# OpIoT_jetson_v_1_4.net
KiCad netlist of a schematic drawn in EAGLE
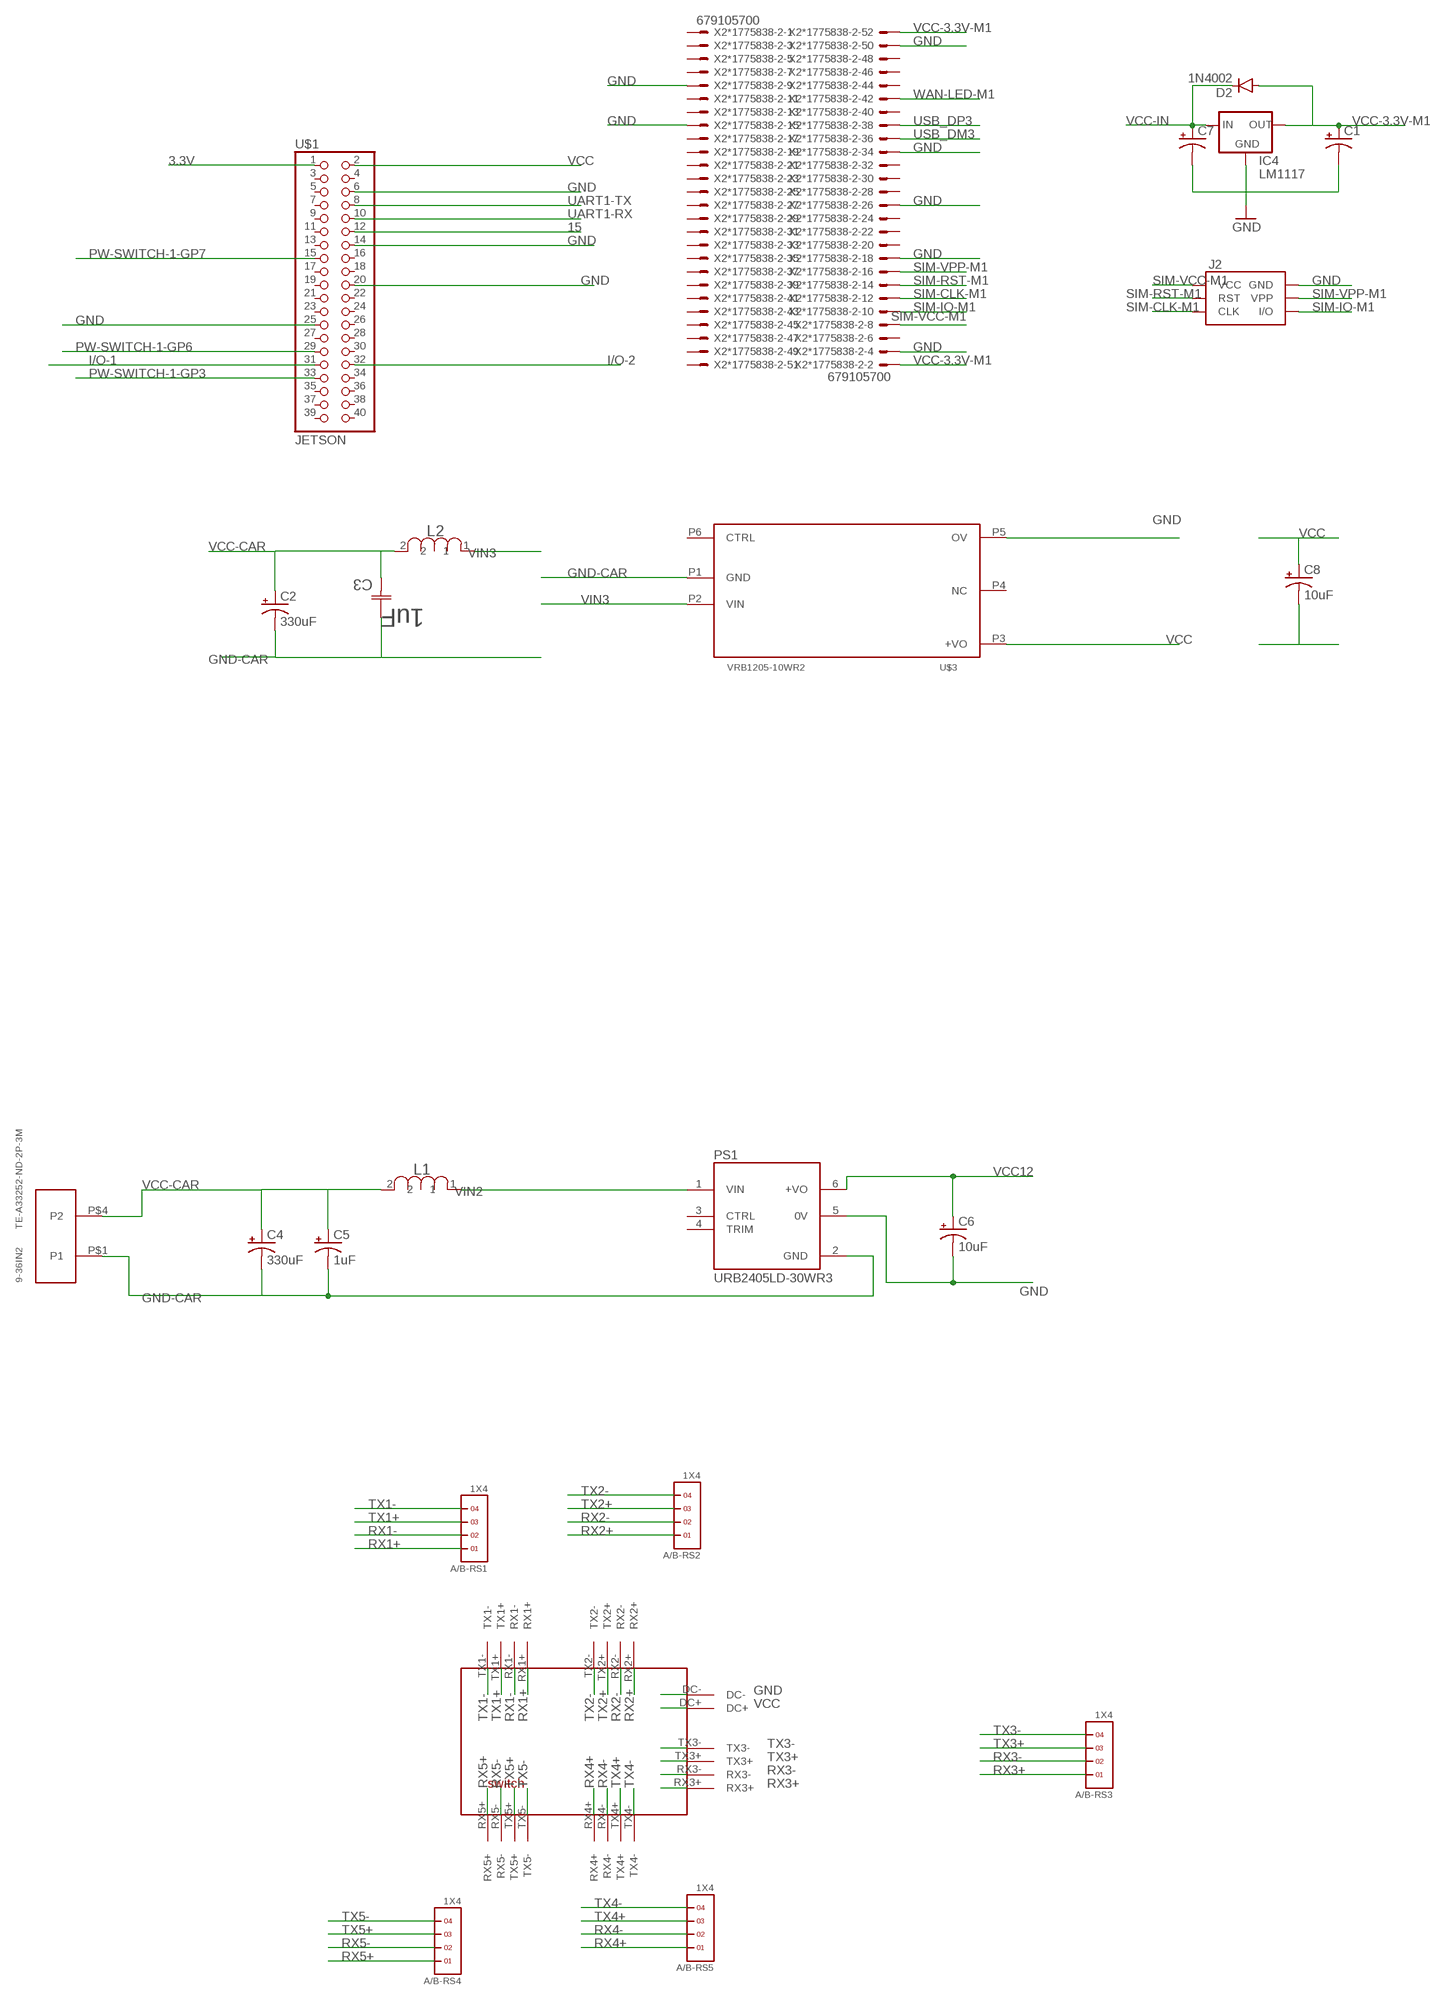
[diagram p0: schematic, sheet 1, part 1 of 2]
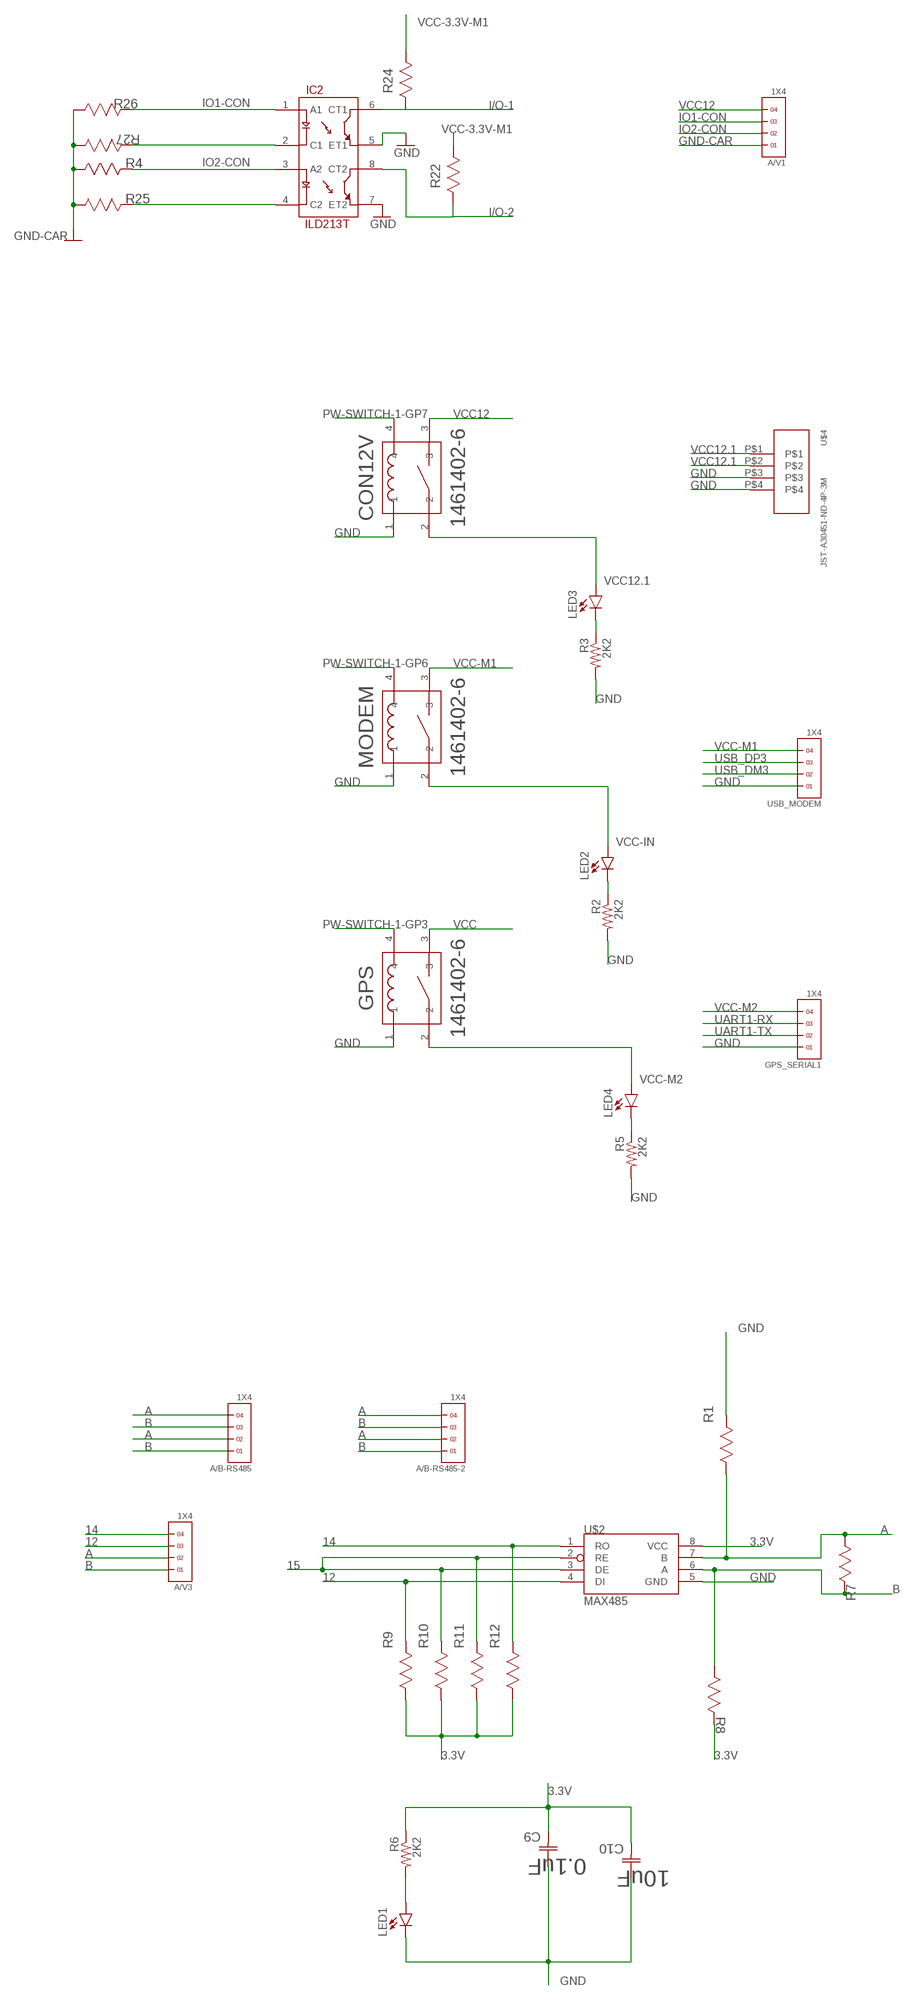
[diagram p1: schematic, sheet 1, part 2 of 2]

(export (version "E")
  (design (tool "Eeschema 10.0.6"))
  (components
    (comp (ref "9-36IN2")
      (value "TE-A33252-ND-2P-3M")
      (footprint "eagle-import:TE-A33252-ND-2P-3M")
      (libsource (lib "eagle-import") (part "TE-A33252-ND-2P-3M"))
    )
    (comp (ref "A/B-RS1")
      (value "1X4")
      (footprint "eagle-import:1X4")
      (libsource (lib "eagle-import") (part "1X4"))
    )
    (comp (ref "A/B-RS2")
      (value "1X4")
      (footprint "eagle-import:1X4")
      (libsource (lib "eagle-import") (part "1X4"))
    )
    (comp (ref "A/B-RS3")
      (value "1X4")
      (footprint "eagle-import:1X4")
      (libsource (lib "eagle-import") (part "1X4"))
    )
    (comp (ref "A/B-RS4")
      (value "1X4")
      (footprint "eagle-import:1X4")
      (libsource (lib "eagle-import") (part "1X4"))
    )
    (comp (ref "A/B-RS5")
      (value "1X4")
      (footprint "eagle-import:1X4")
      (libsource (lib "eagle-import") (part "1X4"))
    )
    (comp (ref "A/B-RS485")
      (value "1X4")
      (footprint "eagle-import:1X4")
      (libsource (lib "eagle-import") (part "1X4"))
    )
    (comp (ref "A/B-RS485-2")
      (value "1X4")
      (footprint "eagle-import:1X4")
      (libsource (lib "eagle-import") (part "1X4"))
    )
    (comp (ref "A/V1")
      (value "1X4")
      (footprint "eagle-import:1X4")
      (libsource (lib "eagle-import") (part "1X4"))
    )
    (comp (ref "A/V3")
      (value "1X4")
      (footprint "eagle-import:1X4")
      (libsource (lib "eagle-import") (part "1X4"))
    )
    (comp (ref "C1")
      (value "CAP_POL1206-KIT")
      (footprint "eagle-import:EIA3216-KIT")
      (libsource (lib "eagle-import") (part "CAP_POL1206-KIT"))
    )
    (comp (ref "C2")
      (value "330uF")
      (footprint "eagle-import:UD-10X10_NICHICON")
      (libsource (lib "eagle-import") (part "CPOL-USUD-10X10"))
    )
    (comp (ref "C3")
      (value "1uF")
      (footprint "eagle-import:CAPC3216X110N")
      (fields (field (name "MPN") "C1206C105K5RACTU") (field (name "TOLERANCE") "±10%"))
      (libsource (lib "eagle-import") (part "C1206C105K5RACTU"))
    )
    (comp (ref "C4")
      (value "330uF")
      (footprint "eagle-import:UD-10X10_NICHICON")
      (libsource (lib "eagle-import") (part "CPOL-USUD-10X10"))
    )
    (comp (ref "C5")
      (value "1uF")
      (footprint "eagle-import:EIA3216-KIT")
      (libsource (lib "eagle-import") (part "CAP_POL1206-KIT"))
    )
    (comp (ref "C6")
      (value "10uF")
      (footprint "eagle-import:EIA3216-KIT")
      (libsource (lib "eagle-import") (part "CAP_POL1206-KIT"))
    )
    (comp (ref "C7")
      (value "CAP_POL1206-KIT")
      (footprint "eagle-import:EIA3216-KIT")
      (libsource (lib "eagle-import") (part "CAP_POL1206-KIT"))
    )
    (comp (ref "C8")
      (value "10uF")
      (footprint "eagle-import:EIA3216-KIT")
      (libsource (lib "eagle-import") (part "CAP_POL1206-KIT"))
    )
    (comp (ref "C9")
      (value "0.1uF")
      (footprint "eagle-import:CAPC3216X110N")
      (fields (field (name "MPN") "C1206C105K5RACTU") (field (name "TOLERANCE") "±10%"))
      (libsource (lib "eagle-import") (part "C1206C105K5RACTU"))
    )
    (comp (ref "C10")
      (value "10uF")
      (footprint "eagle-import:CAPC3216X110N")
      (fields (field (name "MPN") "C1206C105K5RACTU") (field (name "TOLERANCE") "±10%"))
      (libsource (lib "eagle-import") (part "C1206C105K5RACTU"))
    )
    (comp (ref "CON12V")
      (value "1461402-6")
      (footprint "eagle-import:RELAY_1461402-6")
      (fields (field (name "MF") "TE Connectivity") (field (name "MP") "OJE-SH-112HM,000"))
      (libsource (lib "eagle-import") (part "1461402-6"))
    )
    (comp (ref "D2")
      (value "1N4002")
      (footprint "eagle-import:SMA-DIODE-KIT")
      (libsource (lib "eagle-import") (part "DIODESMA-KIT"))
    )
    (comp (ref "GPS")
      (value "1461402-6")
      (footprint "eagle-import:RELAY_1461402-6")
      (fields (field (name "MF") "TE Connectivity") (field (name "MP") "OJE-SH-112HM,000"))
      (libsource (lib "eagle-import") (part "1461402-6"))
    )
    (comp (ref "GPS_SERIAL1")
      (value "1X4")
      (footprint "eagle-import:1X4")
      (libsource (lib "eagle-import") (part "1X4"))
    )
    (comp (ref "IC2")
      (value "ILD213T")
      (footprint "eagle-import:SO08")
      (libsource (lib "eagle-import") (part "ILD213T"))
    )
    (comp (ref "IC4")
      (value "LM1117")
      (footprint "eagle-import:SOT223")
      (fields (field (name "MF") "Texas Instruments") (field (name "MP") "LM1117MP-3.3/NOPB"))
      (libsource (lib "eagle-import") (part "LM1117"))
    )
    (comp (ref "J2")
      (value "SIMHOLDERSIM")
      (footprint "eagle-import:SIMHOLDER")
      (libsource (lib "eagle-import") (part "SIMHOLDERSIM"))
    )
    (comp (ref "L1")
      (value "4.7uH")
      (footprint "eagle-import:INDC3225X22N")
      (fields (field (name "MPN") "PM1210-1R0J-RC") (field (name "TOLERANCE") "±5 %"))
      (libsource (lib "eagle-import") (part "PM1210-1R0J-RC"))
    )
    (comp (ref "L2")
      (value "4.7uH")
      (footprint "eagle-import:INDC3225X22N")
      (fields (field (name "MPN") "PM1210-1R0J-RC") (field (name "TOLERANCE") "±5 %"))
      (libsource (lib "eagle-import") (part "PM1210-1R0J-RC"))
    )
    (comp (ref "LED1")
      (value "LEDCHIPLED_1206")
      (footprint "eagle-import:CHIPLED_1206")
      (libsource (lib "eagle-import") (part "LEDCHIPLED_1206"))
    )
    (comp (ref "LED2")
      (value "LEDCHIPLED_1206")
      (footprint "eagle-import:CHIPLED_1206")
      (libsource (lib "eagle-import") (part "LEDCHIPLED_1206"))
    )
    (comp (ref "LED3")
      (value "LEDCHIPLED_1206")
      (footprint "eagle-import:CHIPLED_1206")
      (libsource (lib "eagle-import") (part "LEDCHIPLED_1206"))
    )
    (comp (ref "LED4")
      (value "LEDCHIPLED_1206")
      (footprint "eagle-import:CHIPLED_1206")
      (libsource (lib "eagle-import") (part "LEDCHIPLED_1206"))
    )
    (comp (ref "MODEM")
      (value "1461402-6")
      (footprint "eagle-import:RELAY_1461402-6")
      (fields (field (name "MF") "TE Connectivity") (field (name "MP") "OJE-SH-112HM,000"))
      (libsource (lib "eagle-import") (part "1461402-6"))
    )
    (comp (ref "PS1")
      (value "URB2405LD-30WR3")
      (footprint "eagle-import:CONV_URB2405LD-30WR3")
      (fields (field (name "MF") "MORNSUN"))
      (libsource (lib "eagle-import") (part "URB2405LD-30WR3"))
    )
    (comp (ref "R1")
      (value "20K")
      (footprint "eagle-import:RESC3216X71N")
      (fields (field (name "MPN") "ERJ-8ENF1501V") (field (name "TOLERANCE") "±1 %"))
      (libsource (lib "eagle-import") (part "ERJ-8ENF1501V"))
    )
    (comp (ref "R2")
      (value "2K2")
      (footprint "eagle-import:M1206")
      (libsource (lib "eagle-import") (part "R-US_M1206"))
    )
    (comp (ref "R3")
      (value "2K2")
      (footprint "eagle-import:M1206")
      (libsource (lib "eagle-import") (part "R-US_M1206"))
    )
    (comp (ref "R4")
      (value "4K7")
      (footprint "eagle-import:RESC3216X71N")
      (fields (field (name "MPN") "ERJ-8ENF1501V") (field (name "TOLERANCE") "±1 %"))
      (libsource (lib "eagle-import") (part "ERJ-8ENF1501V"))
    )
    (comp (ref "R5")
      (value "2K2")
      (footprint "eagle-import:M1206")
      (libsource (lib "eagle-import") (part "R-US_M1206"))
    )
    (comp (ref "R6")
      (value "2K2")
      (footprint "eagle-import:M1206")
      (libsource (lib "eagle-import") (part "R-US_M1206"))
    )
    (comp (ref "R7")
      (value "120")
      (footprint "eagle-import:RESC3216X71N")
      (fields (field (name "MPN") "ERJ-8ENF1501V") (field (name "TOLERANCE") "±1 %"))
      (libsource (lib "eagle-import") (part "ERJ-8ENF1501V"))
    )
    (comp (ref "R8")
      (value "20k")
      (footprint "eagle-import:RESC3216X71N")
      (fields (field (name "MPN") "ERJ-8ENF1501V") (field (name "TOLERANCE") "±1 %"))
      (libsource (lib "eagle-import") (part "ERJ-8ENF1501V"))
    )
    (comp (ref "R9")
      (value "10k")
      (footprint "eagle-import:RESC3216X71N")
      (fields (field (name "MPN") "ERJ-8ENF1501V") (field (name "TOLERANCE") "±1 %"))
      (libsource (lib "eagle-import") (part "ERJ-8ENF1501V"))
    )
    (comp (ref "R10")
      (value "10k")
      (footprint "eagle-import:RESC3216X71N")
      (fields (field (name "MPN") "ERJ-8ENF1501V") (field (name "TOLERANCE") "±1 %"))
      (libsource (lib "eagle-import") (part "ERJ-8ENF1501V"))
    )
    (comp (ref "R11")
      (value "10k")
      (footprint "eagle-import:RESC3216X71N")
      (fields (field (name "MPN") "ERJ-8ENF1501V") (field (name "TOLERANCE") "±1 %"))
      (libsource (lib "eagle-import") (part "ERJ-8ENF1501V"))
    )
    (comp (ref "R12")
      (value "10k")
      (footprint "eagle-import:RESC3216X71N")
      (fields (field (name "MPN") "ERJ-8ENF1501V") (field (name "TOLERANCE") "±1 %"))
      (libsource (lib "eagle-import") (part "ERJ-8ENF1501V"))
    )
    (comp (ref "R22")
      (value "300K")
      (footprint "eagle-import:RESC3216X71N")
      (fields (field (name "MPN") "ERJ-8ENF1501V") (field (name "TOLERANCE") "±1 %"))
      (libsource (lib "eagle-import") (part "ERJ-8ENF1501V"))
    )
    (comp (ref "R24")
      (value "300K")
      (footprint "eagle-import:RESC3216X71N")
      (fields (field (name "MPN") "ERJ-8ENF1501V") (field (name "TOLERANCE") "±1 %"))
      (libsource (lib "eagle-import") (part "ERJ-8ENF1501V"))
    )
    (comp (ref "R25")
      (value "2.2K")
      (footprint "eagle-import:RESC3216X71N")
      (fields (field (name "MPN") "ERJ-8ENF1501V") (field (name "TOLERANCE") "±1 %"))
      (libsource (lib "eagle-import") (part "ERJ-8ENF1501V"))
    )
    (comp (ref "R26")
      (value "4K7")
      (footprint "eagle-import:RESC3216X71N")
      (fields (field (name "MPN") "ERJ-8ENF1501V") (field (name "TOLERANCE") "±1 %"))
      (libsource (lib "eagle-import") (part "ERJ-8ENF1501V"))
    )
    (comp (ref "R27")
      (value "2.2K")
      (footprint "eagle-import:RESC3216X71N")
      (fields (field (name "MPN") "ERJ-8ENF1501V") (field (name "TOLERANCE") "±1 %"))
      (libsource (lib "eagle-import") (part "ERJ-8ENF1501V"))
    )
    (comp (ref "U$1")
      (value "JETSON")
      (footprint "eagle-import:2X20")
      (libsource (lib "eagle-import") (part "JETSON"))
    )
    (comp (ref "U$2")
      (value "MAX485")
      (footprint "eagle-import:SO08")
      (fields (field (name "MF") "Maxim Integrated"))
      (libsource (lib "eagle-import") (part "MAX485"))
    )
    (comp (ref "U$3")
      (value "VRB1205-10WR2")
      (footprint "eagle-import:MORNSUN-5V")
      (libsource (lib "eagle-import") (part "VRB1205-10WR2"))
    )
    (comp (ref "U$4")
      (value "JST-A30451-ND-4P-3M")
      (footprint "eagle-import:TE-A30451-4P-TH-3M")
      (libsource (lib "eagle-import") (part "JST-A30451-ND-4P-3M"))
    )
    (comp (ref "U$6")
      (value "SWITCH")
      (footprint "eagle-import:JP4")
      (libsource (lib "eagle-import") (part "SWITCH"))
    )
    (comp (ref "USB_MODEM")
      (value "1X4")
      (footprint "eagle-import:1X4")
      (libsource (lib "eagle-import") (part "1X4"))
    )
    (comp (ref "X2*1775838-2")
      (value "679105700")
      (footprint "eagle-import:679105700")
      (fields (field (name "MF") "MOLEX") (field (name "MPN") "67910-5700"))
      (libsource (lib "eagle-import") (part "679105700"))
    )
  )
  (nets
    (net (code "1") (name "/3.3V") (class "Default")
      (node (ref "C10") (pin "2") (pinfunction "C2_2") (pintype "passive"))
      (node (ref "C9") (pin "2") (pinfunction "C2_2") (pintype "passive"))
      (node (ref "R10") (pin "2") (pinfunction "R2_2") (pintype "passive"))
      (node (ref "R11") (pin "2") (pinfunction "R2_2") (pintype "passive"))
      (node (ref "R12") (pin "2") (pinfunction "R2_2") (pintype "passive"))
      (node (ref "R6") (pin "1") (pinfunction "1_1") (pintype "passive"))
      (node (ref "R8") (pin "1") (pinfunction "R1_1") (pintype "passive"))
      (node (ref "R9") (pin "2") (pinfunction "R2_2") (pintype "passive"))
      (node (ref "U$1") (pin "1") (pinfunction "1_1") (pintype "passive"))
      (node (ref "U$2") (pin "8") (pinfunction "VCC_8") (pintype "bidirectional"))
    )
    (net (code "2") (name "/12") (class "Default")
      (node (ref "A/V3") (pin "3") (pinfunction "3_3") (pintype "bidirectional"))
      (node (ref "R9") (pin "1") (pinfunction "R1_1") (pintype "passive"))
      (node (ref "U$2") (pin "4") (pinfunction "DI_4") (pintype "bidirectional"))
    )
    (net (code "3") (name "/14") (class "Default")
      (node (ref "A/V3") (pin "4") (pinfunction "4_4") (pintype "bidirectional"))
      (node (ref "R12") (pin "1") (pinfunction "R1_1") (pintype "passive"))
      (node (ref "U$2") (pin "1") (pinfunction "RO_1") (pintype "bidirectional"))
    )
    (net (code "4") (name "/15") (class "Default")
      (node (ref "R10") (pin "1") (pinfunction "R1_1") (pintype "passive"))
      (node (ref "R11") (pin "1") (pinfunction "R1_1") (pintype "passive"))
      (node (ref "U$1") (pin "12") (pinfunction "12_12") (pintype "passive"))
      (node (ref "U$2") (pin "2") (pinfunction "RE_2") (pintype "bidirectional"))
      (node (ref "U$2") (pin "3") (pinfunction "DE_3") (pintype "bidirectional"))
    )
    (net (code "5") (name "/A") (class "Default")
      (node (ref "A/B-RS485") (pin "2") (pinfunction "2_2") (pintype "bidirectional"))
      (node (ref "A/B-RS485") (pin "4") (pinfunction "4_4") (pintype "bidirectional"))
      (node (ref "A/B-RS485-2") (pin "2") (pinfunction "2_2") (pintype "bidirectional"))
      (node (ref "A/B-RS485-2") (pin "4") (pinfunction "4_4") (pintype "bidirectional"))
      (node (ref "A/V3") (pin "2") (pinfunction "2_2") (pintype "bidirectional"))
      (node (ref "R1") (pin "2") (pinfunction "R2_2") (pintype "passive"))
      (node (ref "R7") (pin "1") (pinfunction "R1_1") (pintype "passive"))
      (node (ref "U$2") (pin "7") (pinfunction "B_7") (pintype "bidirectional"))
    )
    (net (code "6") (name "/B") (class "Default")
      (node (ref "A/B-RS485") (pin "1") (pinfunction "1_1") (pintype "bidirectional"))
      (node (ref "A/B-RS485") (pin "3") (pinfunction "3_3") (pintype "bidirectional"))
      (node (ref "A/B-RS485-2") (pin "1") (pinfunction "1_1") (pintype "bidirectional"))
      (node (ref "A/B-RS485-2") (pin "3") (pinfunction "3_3") (pintype "bidirectional"))
      (node (ref "A/V3") (pin "1") (pinfunction "1_1") (pintype "bidirectional"))
      (node (ref "R7") (pin "2") (pinfunction "R2_2") (pintype "passive"))
      (node (ref "R8") (pin "2") (pinfunction "R2_2") (pintype "passive"))
      (node (ref "U$2") (pin "6") (pinfunction "A_6") (pintype "bidirectional"))
    )
    (net (code "7") (name "/IO1-CON") (class "Default")
      (node (ref "A/V1") (pin "3") (pinfunction "3_3") (pintype "bidirectional"))
      (node (ref "IC2") (pin "1") (pinfunction "A1_1") (pintype "bidirectional"))
      (node (ref "R26") (pin "1") (pinfunction "R1_1") (pintype "passive"))
    )
    (net (code "8") (name "/IO2-CON") (class "Default")
      (node (ref "A/V1") (pin "2") (pinfunction "2_2") (pintype "bidirectional"))
      (node (ref "IC2") (pin "3") (pinfunction "A2_3") (pintype "bidirectional"))
      (node (ref "R4") (pin "1") (pinfunction "R1_1") (pintype "passive"))
    )
    (net (code "9") (name "/I{slash}O-1") (class "Default")
      (node (ref "IC2") (pin "6") (pinfunction "CT1_6") (pintype "bidirectional"))
      (node (ref "R24") (pin "2") (pinfunction "R2_2") (pintype "passive"))
      (node (ref "U$1") (pin "31") (pinfunction "31_31") (pintype "passive"))
    )
    (net (code "10") (name "/I{slash}O-2") (class "Default")
      (node (ref "IC2") (pin "8") (pinfunction "CT2_8") (pintype "bidirectional"))
      (node (ref "R22") (pin "2") (pinfunction "R2_2") (pintype "passive"))
      (node (ref "U$1") (pin "32") (pinfunction "32_32") (pintype "passive"))
    )
    (net (code "11") (name "/PW-SWITCH-1-GP3") (class "Default")
      (node (ref "GPS") (pin "4") (pinfunction "4_4") (pintype "passive"))
      (node (ref "U$1") (pin "33") (pinfunction "33_33") (pintype "passive"))
    )
    (net (code "12") (name "/PW-SWITCH-1-GP6") (class "Default")
      (node (ref "MODEM") (pin "4") (pinfunction "4_4") (pintype "passive"))
      (node (ref "U$1") (pin "29") (pinfunction "29_29") (pintype "passive"))
    )
    (net (code "13") (name "/PW-SWITCH-1-GP7") (class "Default")
      (node (ref "CON12V") (pin "4") (pinfunction "4_4") (pintype "passive"))
      (node (ref "U$1") (pin "15") (pinfunction "15_15") (pintype "passive"))
    )
    (net (code "14") (name "/RX1+") (class "Default")
      (node (ref "A/B-RS1") (pin "1") (pinfunction "1_1") (pintype "bidirectional"))
      (node (ref "U$6") (pin "RX1+") (pinfunction "RX1+_RX1+") (pintype "bidirectional"))
    )
    (net (code "15") (name "/RX1-") (class "Default")
      (node (ref "A/B-RS1") (pin "2") (pinfunction "2_2") (pintype "bidirectional"))
      (node (ref "U$6") (pin "RX1-") (pinfunction "RX1-_RX1-") (pintype "bidirectional"))
    )
    (net (code "16") (name "/RX2+") (class "Default")
      (node (ref "A/B-RS2") (pin "1") (pinfunction "1_1") (pintype "bidirectional"))
      (node (ref "U$6") (pin "RX2+") (pinfunction "RX2+_RX2+") (pintype "bidirectional"))
    )
    (net (code "17") (name "/RX2-") (class "Default")
      (node (ref "A/B-RS2") (pin "2") (pinfunction "2_2") (pintype "bidirectional"))
      (node (ref "U$6") (pin "RX2-") (pinfunction "RX2-_RX2-") (pintype "bidirectional"))
    )
    (net (code "18") (name "/RX3+") (class "Default")
      (node (ref "A/B-RS3") (pin "1") (pinfunction "1_1") (pintype "bidirectional"))
      (node (ref "U$6") (pin "RX3+") (pinfunction "RX3+_RX3+") (pintype "bidirectional"))
    )
    (net (code "19") (name "/RX3-") (class "Default")
      (node (ref "A/B-RS3") (pin "2") (pinfunction "2_2") (pintype "bidirectional"))
      (node (ref "U$6") (pin "RX3-") (pinfunction "RX3-_RX3-") (pintype "bidirectional"))
    )
    (net (code "20") (name "/RX4+") (class "Default")
      (node (ref "A/B-RS5") (pin "1") (pinfunction "1_1") (pintype "bidirectional"))
      (node (ref "U$6") (pin "RX4+") (pinfunction "RX4+_RX4+") (pintype "bidirectional"))
    )
    (net (code "21") (name "/RX4-") (class "Default")
      (node (ref "A/B-RS5") (pin "2") (pinfunction "2_2") (pintype "bidirectional"))
      (node (ref "U$6") (pin "RX4-") (pinfunction "RX4-_RX4-") (pintype "bidirectional"))
    )
    (net (code "22") (name "/RX5+") (class "Default")
      (node (ref "A/B-RS4") (pin "1") (pinfunction "1_1") (pintype "bidirectional"))
      (node (ref "U$6") (pin "RX5+") (pinfunction "RX5+_RX5+") (pintype "bidirectional"))
    )
    (net (code "23") (name "/RX5-") (class "Default")
      (node (ref "A/B-RS4") (pin "2") (pinfunction "2_2") (pintype "bidirectional"))
      (node (ref "U$6") (pin "RX5-") (pinfunction "RX5-_RX5-") (pintype "bidirectional"))
    )
    (net (code "24") (name "/SIM-CLK-M1") (class "Default")
      (node (ref "J2") (pin "C3") (pinfunction "CLK_C3") (pintype "input"))
      (node (ref "X2*1775838-2") (pin "12") (pinfunction "S_12") (pintype "passive"))
    )
    (net (code "25") (name "/SIM-IO-M1") (class "Default")
      (node (ref "J2") (pin "C7") (pinfunction "I/O_C7") (pintype "bidirectional"))
      (node (ref "X2*1775838-2") (pin "10") (pinfunction "S_10") (pintype "passive"))
    )
    (net (code "26") (name "/SIM-RST-M1") (class "Default")
      (node (ref "J2") (pin "C2") (pinfunction "RST_C2") (pintype "input"))
      (node (ref "X2*1775838-2") (pin "14") (pinfunction "S_14") (pintype "passive"))
    )
    (net (code "27") (name "/SIM-VCC-M1") (class "Default")
      (node (ref "J2") (pin "C1") (pinfunction "VCC_C1") (pintype "power_in"))
      (node (ref "X2*1775838-2") (pin "8") (pinfunction "S_8") (pintype "passive"))
    )
    (net (code "28") (name "/SIM-VPP-M1") (class "Default")
      (node (ref "J2") (pin "C6") (pinfunction "VPP_C6") (pintype "input"))
      (node (ref "X2*1775838-2") (pin "16") (pinfunction "S_16") (pintype "passive"))
    )
    (net (code "29") (name "/TX1+") (class "Default")
      (node (ref "A/B-RS1") (pin "3") (pinfunction "3_3") (pintype "bidirectional"))
      (node (ref "U$6") (pin "TX1+") (pinfunction "TX1+_TX1+") (pintype "bidirectional"))
    )
    (net (code "30") (name "/TX1-") (class "Default")
      (node (ref "A/B-RS1") (pin "4") (pinfunction "4_4") (pintype "bidirectional"))
      (node (ref "U$6") (pin "TX1-") (pinfunction "TX1-_TX1-") (pintype "bidirectional"))
    )
    (net (code "31") (name "/TX2+") (class "Default")
      (node (ref "A/B-RS2") (pin "3") (pinfunction "3_3") (pintype "bidirectional"))
      (node (ref "U$6") (pin "TX2+") (pinfunction "TX2+_TX2+") (pintype "bidirectional"))
    )
    (net (code "32") (name "/TX2-") (class "Default")
      (node (ref "A/B-RS2") (pin "4") (pinfunction "4_4") (pintype "bidirectional"))
      (node (ref "U$6") (pin "TX2-") (pinfunction "TX2-_TX2-") (pintype "bidirectional"))
    )
    (net (code "33") (name "/TX3+") (class "Default")
      (node (ref "A/B-RS3") (pin "3") (pinfunction "3_3") (pintype "bidirectional"))
      (node (ref "U$6") (pin "TX3+") (pinfunction "TX3+_TX3+") (pintype "bidirectional"))
    )
    (net (code "34") (name "/TX3-") (class "Default")
      (node (ref "A/B-RS3") (pin "4") (pinfunction "4_4") (pintype "bidirectional"))
      (node (ref "U$6") (pin "TX3-") (pinfunction "TX3-_TX3-") (pintype "bidirectional"))
    )
    (net (code "35") (name "/TX4+") (class "Default")
      (node (ref "A/B-RS5") (pin "3") (pinfunction "3_3") (pintype "bidirectional"))
      (node (ref "U$6") (pin "TX4+") (pinfunction "TX4+_TX4+") (pintype "bidirectional"))
    )
    (net (code "36") (name "/TX4-") (class "Default")
      (node (ref "A/B-RS5") (pin "4") (pinfunction "4_4") (pintype "bidirectional"))
      (node (ref "U$6") (pin "TX4-") (pinfunction "TX4-_TX4-") (pintype "bidirectional"))
    )
    (net (code "37") (name "/TX5+") (class "Default")
      (node (ref "A/B-RS4") (pin "3") (pinfunction "3_3") (pintype "bidirectional"))
      (node (ref "U$6") (pin "TX5+") (pinfunction "TX5+_TX5+") (pintype "bidirectional"))
    )
    (net (code "38") (name "/TX5-") (class "Default")
      (node (ref "A/B-RS4") (pin "4") (pinfunction "4_4") (pintype "bidirectional"))
      (node (ref "U$6") (pin "TX5-") (pinfunction "TX5-_TX5-") (pintype "bidirectional"))
    )
    (net (code "39") (name "/UART1-RX") (class "Default")
      (node (ref "GPS_SERIAL1") (pin "3") (pinfunction "3_3") (pintype "bidirectional"))
      (node (ref "U$1") (pin "10") (pinfunction "10_10") (pintype "passive"))
    )
    (net (code "40") (name "/UART1-TX") (class "Default")
      (node (ref "GPS_SERIAL1") (pin "2") (pinfunction "2_2") (pintype "bidirectional"))
      (node (ref "U$1") (pin "8") (pinfunction "8_8") (pintype "passive"))
    )
    (net (code "41") (name "/USB_DM3") (class "Default")
      (node (ref "USB_MODEM") (pin "2") (pinfunction "2_2") (pintype "bidirectional"))
      (node (ref "X2*1775838-2") (pin "36") (pinfunction "S_36") (pintype "passive"))
    )
    (net (code "42") (name "/USB_DP3") (class "Default")
      (node (ref "USB_MODEM") (pin "3") (pinfunction "3_3") (pintype "bidirectional"))
      (node (ref "X2*1775838-2") (pin "38") (pinfunction "S_38") (pintype "passive"))
    )
    (net (code "43") (name "/VCC") (class "Default")
      (node (ref "C8") (pin "A") (pinfunction "+_A") (pintype "passive"))
      (node (ref "GPS") (pin "3") (pinfunction "3_3") (pintype "passive"))
      (node (ref "U$1") (pin "2") (pinfunction "2_2") (pintype "passive"))
      (node (ref "U$3") (pin "P3") (pinfunction "+VO_P3") (pintype "output"))
      (node (ref "U$6") (pin "DC+") (pinfunction "DC+_DC+") (pintype "bidirectional"))
    )
    (net (code "44") (name "/VCC-3.3V-M1") (class "Default")
      (node (ref "C1") (pin "A") (pinfunction "+_A") (pintype "passive"))
      (node (ref "D2") (pin "A") (pinfunction "A_A") (pintype "passive"))
      (node (ref "IC4") (pin "2") (pinfunction "OUT_2") (pintype "passive"))
      (node (ref "R22") (pin "1") (pinfunction "R1_1") (pintype "passive"))
      (node (ref "R24") (pin "1") (pinfunction "R1_1") (pintype "passive"))
      (node (ref "X2*1775838-2") (pin "2") (pinfunction "S_2") (pintype "passive"))
      (node (ref "X2*1775838-2") (pin "52") (pinfunction "S_52") (pintype "passive"))
    )
    (net (code "45") (name "/VCC-CAR") (class "Default")
      (node (ref "9-36IN2") (pin "P$4") (pinfunction "P2_P$4") (pintype "bidirectional"))
      (node (ref "C2") (pin "+") (pinfunction "+_+") (pintype "passive"))
      (node (ref "C3") (pin "2") (pinfunction "C2_2") (pintype "passive"))
      (node (ref "C4") (pin "+") (pinfunction "+_+") (pintype "passive"))
      (node (ref "C5") (pin "A") (pinfunction "+_A") (pintype "passive"))
      (node (ref "L1") (pin "2") (pinfunction "2_2") (pintype "passive"))
      (node (ref "L2") (pin "2") (pinfunction "2_2") (pintype "passive"))
    )
    (net (code "46") (name "/VCC-IN") (class "Default")
      (node (ref "C7") (pin "A") (pinfunction "+_A") (pintype "passive"))
      (node (ref "D2") (pin "C") (pinfunction "C_C") (pintype "passive"))
      (node (ref "IC4") (pin "3") (pinfunction "IN_3") (pintype "input"))
      (node (ref "LED2") (pin "A") (pinfunction "A_A") (pintype "passive"))
      (node (ref "MODEM") (pin "2") (pinfunction "2_2") (pintype "passive"))
    )
    (net (code "47") (name "/VCC-M1") (class "Default")
      (node (ref "MODEM") (pin "3") (pinfunction "3_3") (pintype "passive"))
      (node (ref "USB_MODEM") (pin "4") (pinfunction "4_4") (pintype "bidirectional"))
    )
    (net (code "48") (name "/VCC-M2") (class "Default")
      (node (ref "GPS") (pin "2") (pinfunction "2_2") (pintype "passive"))
      (node (ref "GPS_SERIAL1") (pin "4") (pinfunction "4_4") (pintype "bidirectional"))
      (node (ref "LED4") (pin "A") (pinfunction "A_A") (pintype "passive"))
    )
    (net (code "49") (name "/VCC12") (class "Default")
      (node (ref "A/V1") (pin "4") (pinfunction "4_4") (pintype "bidirectional"))
      (node (ref "C6") (pin "A") (pinfunction "+_A") (pintype "passive"))
      (node (ref "CON12V") (pin "3") (pinfunction "3_3") (pintype "passive"))
      (node (ref "PS1") (pin "6") (pinfunction "+VO_6") (pintype "output"))
    )
    (net (code "50") (name "/VCC12.1") (class "Default")
      (node (ref "CON12V") (pin "2") (pinfunction "2_2") (pintype "passive"))
      (node (ref "LED3") (pin "A") (pinfunction "A_A") (pintype "passive"))
      (node (ref "U$4") (pin "P$1") (pinfunction "P$1_P$1") (pintype "bidirectional"))
      (node (ref "U$4") (pin "P$2") (pinfunction "P$2_P$2") (pintype "bidirectional"))
    )
    (net (code "51") (name "/VIN2") (class "Default")
      (node (ref "L1") (pin "1") (pinfunction "1_1") (pintype "passive"))
      (node (ref "PS1") (pin "1") (pinfunction "VIN_1") (pintype "input"))
    )
    (net (code "52") (name "/VIN3") (class "Default")
      (node (ref "L2") (pin "1") (pinfunction "1_1") (pintype "passive"))
      (node (ref "U$3") (pin "P2") (pinfunction "VIN_P2") (pintype "bidirectional"))
    )
    (net (code "53") (name "/WAN-LED-M1") (class "Default")
      (node (ref "X2*1775838-2") (pin "42") (pinfunction "S_42") (pintype "passive"))
    )
    (net (code "54") (name "GND") (class "Default")
      (node (ref "C1") (pin "C") (pinfunction "-_C") (pintype "passive"))
      (node (ref "C10") (pin "1") (pinfunction "C1_1") (pintype "passive"))
      (node (ref "C6") (pin "C") (pinfunction "-_C") (pintype "passive"))
      (node (ref "C7") (pin "C") (pinfunction "-_C") (pintype "passive"))
      (node (ref "C8") (pin "C") (pinfunction "-_C") (pintype "passive"))
      (node (ref "C9") (pin "1") (pinfunction "C1_1") (pintype "passive"))
      (node (ref "CON12V") (pin "1") (pinfunction "1_1") (pintype "passive"))
      (node (ref "GPS") (pin "1") (pinfunction "1_1") (pintype "passive"))
      (node (ref "GPS_SERIAL1") (pin "1") (pinfunction "1_1") (pintype "bidirectional"))
      (node (ref "IC2") (pin "5") (pinfunction "ET1_5") (pintype "bidirectional"))
      (node (ref "IC2") (pin "7") (pinfunction "ET2_7") (pintype "bidirectional"))
      (node (ref "IC4") (pin "1") (pinfunction "GND_1") (pintype "input"))
      (node (ref "J2") (pin "C5") (pinfunction "GND_C5") (pintype "power_in"))
      (node (ref "LED1") (pin "C") (pinfunction "C_C") (pintype "passive"))
      (node (ref "MODEM") (pin "1") (pinfunction "1_1") (pintype "passive"))
      (node (ref "PS1") (pin "5") (pinfunction "0V_5") (pintype "output"))
      (node (ref "R1") (pin "1") (pinfunction "R1_1") (pintype "passive"))
      (node (ref "R2") (pin "2") (pinfunction "2_2") (pintype "passive"))
      (node (ref "R3") (pin "2") (pinfunction "2_2") (pintype "passive"))
      (node (ref "R5") (pin "2") (pinfunction "2_2") (pintype "passive"))
      (node (ref "U$1") (pin "14") (pinfunction "14_14") (pintype "passive"))
      (node (ref "U$1") (pin "20") (pinfunction "20_20") (pintype "passive"))
      (node (ref "U$1") (pin "25") (pinfunction "25_25") (pintype "passive"))
      (node (ref "U$1") (pin "6") (pinfunction "6_6") (pintype "passive"))
      (node (ref "U$2") (pin "5") (pinfunction "GND_5") (pintype "bidirectional"))
      (node (ref "U$3") (pin "P5") (pinfunction "OV_P5") (pintype "output"))
      (node (ref "U$4") (pin "P$3") (pinfunction "P$3_P$3") (pintype "bidirectional"))
      (node (ref "U$4") (pin "P$4") (pinfunction "P$4_P$4") (pintype "bidirectional"))
      (node (ref "U$6") (pin "DC-") (pinfunction "DC-_DC-") (pintype "bidirectional"))
      (node (ref "USB_MODEM") (pin "1") (pinfunction "1_1") (pintype "bidirectional"))
      (node (ref "X2*1775838-2") (pin "15") (pinfunction "S_15") (pintype "passive"))
      (node (ref "X2*1775838-2") (pin "18") (pinfunction "S_18") (pintype "passive"))
      (node (ref "X2*1775838-2") (pin "26") (pinfunction "S_26") (pintype "passive"))
      (node (ref "X2*1775838-2") (pin "34") (pinfunction "S_34") (pintype "passive"))
      (node (ref "X2*1775838-2") (pin "4") (pinfunction "S_4") (pintype "passive"))
      (node (ref "X2*1775838-2") (pin "50") (pinfunction "S_50") (pintype "passive"))
      (node (ref "X2*1775838-2") (pin "9") (pinfunction "S_9") (pintype "passive"))
    )
    (net (code "55") (name "GND-CAR") (class "Default")
      (node (ref "9-36IN2") (pin "P$1") (pinfunction "P1_P$1") (pintype "bidirectional"))
      (node (ref "A/V1") (pin "1") (pinfunction "1_1") (pintype "bidirectional"))
      (node (ref "C2") (pin "-") (pinfunction "-_-") (pintype "passive"))
      (node (ref "C3") (pin "1") (pinfunction "C1_1") (pintype "passive"))
      (node (ref "C4") (pin "-") (pinfunction "-_-") (pintype "passive"))
      (node (ref "C5") (pin "C") (pinfunction "-_C") (pintype "passive"))
      (node (ref "PS1") (pin "2") (pinfunction "GND_2") (pintype "power_in"))
      (node (ref "R25") (pin "1") (pinfunction "R1_1") (pintype "passive"))
      (node (ref "R26") (pin "2") (pinfunction "R2_2") (pintype "passive"))
      (node (ref "R27") (pin "1") (pinfunction "R1_1") (pintype "passive"))
      (node (ref "R4") (pin "2") (pinfunction "R2_2") (pintype "passive"))
      (node (ref "U$3") (pin "P1") (pinfunction "GND_P1") (pintype "bidirectional"))
    )
    (net (code "56") (name "Net-(IC2-C1)") (class "Default")
      (node (ref "IC2") (pin "2") (pinfunction "C1_2") (pintype "bidirectional"))
      (node (ref "R27") (pin "2") (pinfunction "R2_2") (pintype "passive"))
    )
    (net (code "57") (name "Net-(IC2-C2)") (class "Default")
      (node (ref "IC2") (pin "4") (pinfunction "C2_4") (pintype "bidirectional"))
      (node (ref "R25") (pin "2") (pinfunction "R2_2") (pintype "passive"))
    )
    (net (code "58") (name "Net-(LED1-PadA)") (class "Default")
      (node (ref "LED1") (pin "A") (pinfunction "A_A") (pintype "passive"))
      (node (ref "R6") (pin "2") (pinfunction "2_2") (pintype "passive"))
    )
    (net (code "59") (name "Net-(LED2-PadC)") (class "Default")
      (node (ref "LED2") (pin "C") (pinfunction "C_C") (pintype "passive"))
      (node (ref "R2") (pin "1") (pinfunction "1_1") (pintype "passive"))
    )
    (net (code "60") (name "Net-(LED3-PadC)") (class "Default")
      (node (ref "LED3") (pin "C") (pinfunction "C_C") (pintype "passive"))
      (node (ref "R3") (pin "1") (pinfunction "1_1") (pintype "passive"))
    )
    (net (code "61") (name "Net-(LED4-PadC)") (class "Default")
      (node (ref "LED4") (pin "C") (pinfunction "C_C") (pintype "passive"))
      (node (ref "R5") (pin "1") (pinfunction "1_1") (pintype "passive"))
    )
    (net (code "62") (name "unconnected-(PS1-CTRL-Pad3)") (class "Default")
      (node (ref "PS1") (pin "3") (pinfunction "CTRL_3") (pintype "input"))
    )
    (net (code "63") (name "unconnected-(PS1-TRIM-Pad4)") (class "Default")
      (node (ref "PS1") (pin "4") (pinfunction "TRIM_4") (pintype "input"))
    )
    (net (code "64") (name "unconnected-(U$1-Pad3)") (class "Default")
      (node (ref "U$1") (pin "3") (pinfunction "3_3") (pintype "passive"))
    )
    (net (code "65") (name "unconnected-(U$1-Pad4)") (class "Default")
      (node (ref "U$1") (pin "4") (pinfunction "4_4") (pintype "passive"))
    )
    (net (code "66") (name "unconnected-(U$1-Pad5)") (class "Default")
      (node (ref "U$1") (pin "5") (pinfunction "5_5") (pintype "passive"))
    )
    (net (code "67") (name "unconnected-(U$1-Pad7)") (class "Default")
      (node (ref "U$1") (pin "7") (pinfunction "7_7") (pintype "passive"))
    )
    (net (code "68") (name "unconnected-(U$1-Pad9)") (class "Default")
      (node (ref "U$1") (pin "9") (pinfunction "9_9") (pintype "passive"))
    )
    (net (code "69") (name "unconnected-(U$1-Pad11)") (class "Default")
      (node (ref "U$1") (pin "11") (pinfunction "11_11") (pintype "passive"))
    )
    (net (code "70") (name "unconnected-(U$1-Pad13)") (class "Default")
      (node (ref "U$1") (pin "13") (pinfunction "13_13") (pintype "passive"))
    )
    (net (code "71") (name "unconnected-(U$1-Pad16)") (class "Default")
      (node (ref "U$1") (pin "16") (pinfunction "16_16") (pintype "passive"))
    )
    (net (code "72") (name "unconnected-(U$1-Pad17)") (class "Default")
      (node (ref "U$1") (pin "17") (pinfunction "17_17") (pintype "passive"))
    )
    (net (code "73") (name "unconnected-(U$1-Pad18)") (class "Default")
      (node (ref "U$1") (pin "18") (pinfunction "18_18") (pintype "passive"))
    )
    (net (code "74") (name "unconnected-(U$1-Pad19)") (class "Default")
      (node (ref "U$1") (pin "19") (pinfunction "19_19") (pintype "passive"))
    )
    (net (code "75") (name "unconnected-(U$1-Pad21)") (class "Default")
      (node (ref "U$1") (pin "21") (pinfunction "21_21") (pintype "passive"))
    )
    (net (code "76") (name "unconnected-(U$1-Pad22)") (class "Default")
      (node (ref "U$1") (pin "22") (pinfunction "22_22") (pintype "passive"))
    )
    (net (code "77") (name "unconnected-(U$1-Pad23)") (class "Default")
      (node (ref "U$1") (pin "23") (pinfunction "23_23") (pintype "passive"))
    )
    (net (code "78") (name "unconnected-(U$1-Pad24)") (class "Default")
      (node (ref "U$1") (pin "24") (pinfunction "24_24") (pintype "passive"))
    )
    (net (code "79") (name "unconnected-(U$1-Pad26)") (class "Default")
      (node (ref "U$1") (pin "26") (pinfunction "26_26") (pintype "passive"))
    )
    (net (code "80") (name "unconnected-(U$1-Pad27)") (class "Default")
      (node (ref "U$1") (pin "27") (pinfunction "27_27") (pintype "passive"))
    )
    (net (code "81") (name "unconnected-(U$1-Pad28)") (class "Default")
      (node (ref "U$1") (pin "28") (pinfunction "28_28") (pintype "passive"))
    )
    (net (code "82") (name "unconnected-(U$1-Pad30)") (class "Default")
      (node (ref "U$1") (pin "30") (pinfunction "30_30") (pintype "passive"))
    )
    (net (code "83") (name "unconnected-(U$1-Pad34)") (class "Default")
      (node (ref "U$1") (pin "34") (pinfunction "34_34") (pintype "passive"))
    )
    (net (code "84") (name "unconnected-(U$1-Pad35)") (class "Default")
      (node (ref "U$1") (pin "35") (pinfunction "35_35") (pintype "passive"))
    )
    (net (code "85") (name "unconnected-(U$1-Pad36)") (class "Default")
      (node (ref "U$1") (pin "36") (pinfunction "36_36") (pintype "passive"))
    )
    (net (code "86") (name "unconnected-(U$1-Pad37)") (class "Default")
      (node (ref "U$1") (pin "37") (pinfunction "37_37") (pintype "passive"))
    )
    (net (code "87") (name "unconnected-(U$1-Pad38)") (class "Default")
      (node (ref "U$1") (pin "38") (pinfunction "38_38") (pintype "passive"))
    )
    (net (code "88") (name "unconnected-(U$1-Pad39)") (class "Default")
      (node (ref "U$1") (pin "39") (pinfunction "39_39") (pintype "passive"))
    )
    (net (code "89") (name "unconnected-(U$1-Pad40)") (class "Default")
      (node (ref "U$1") (pin "40") (pinfunction "40_40") (pintype "passive"))
    )
    (net (code "90") (name "unconnected-(U$3-CTRL-PadP6)") (class "Default")
      (node (ref "U$3") (pin "P6") (pinfunction "CTRL_P6") (pintype "bidirectional"))
    )
    (net (code "91") (name "unconnected-(U$3-NC-PadP4)") (class "Default")
      (node (ref "U$3") (pin "P4") (pinfunction "NC_P4") (pintype "output"))
    )
    (net (code "92") (name "unconnected-(X2*1775838-2A-S-Pad1)") (class "Default")
      (node (ref "X2*1775838-2") (pin "1") (pinfunction "S_1") (pintype "passive"))
    )
    (net (code "93") (name "unconnected-(X2*1775838-2AA-S-Pad33)") (class "Default")
      (node (ref "X2*1775838-2") (pin "33") (pinfunction "S_33") (pintype "passive"))
    )
    (net (code "94") (name "unconnected-(X2*1775838-2AC-S-Pad35)") (class "Default")
      (node (ref "X2*1775838-2") (pin "35") (pinfunction "S_35") (pintype "passive"))
    )
    (net (code "95") (name "unconnected-(X2*1775838-2AE-S-Pad37)") (class "Default")
      (node (ref "X2*1775838-2") (pin "37") (pinfunction "S_37") (pintype "passive"))
    )
    (net (code "96") (name "unconnected-(X2*1775838-2AG-S-Pad39)") (class "Default")
      (node (ref "X2*1775838-2") (pin "39") (pinfunction "S_39") (pintype "passive"))
    )
    (net (code "97") (name "unconnected-(X2*1775838-2AI-S-Pad40)") (class "Default")
      (node (ref "X2*1775838-2") (pin "40") (pinfunction "S_40") (pintype "passive"))
    )
    (net (code "98") (name "unconnected-(X2*1775838-2AJ-S-Pad41)") (class "Default")
      (node (ref "X2*1775838-2") (pin "41") (pinfunction "S_41") (pintype "passive"))
    )
    (net (code "99") (name "unconnected-(X2*1775838-2AL-S-Pad43)") (class "Default")
      (node (ref "X2*1775838-2") (pin "43") (pinfunction "S_43") (pintype "passive"))
    )
    (net (code "100") (name "unconnected-(X2*1775838-2AM-S-Pad44)") (class "Default")
      (node (ref "X2*1775838-2") (pin "44") (pinfunction "S_44") (pintype "passive"))
    )
    (net (code "101") (name "unconnected-(X2*1775838-2AN-S-Pad45)") (class "Default")
      (node (ref "X2*1775838-2") (pin "45") (pinfunction "S_45") (pintype "passive"))
    )
    (net (code "102") (name "unconnected-(X2*1775838-2AO-S-Pad46)") (class "Default")
      (node (ref "X2*1775838-2") (pin "46") (pinfunction "S_46") (pintype "passive"))
    )
    (net (code "103") (name "unconnected-(X2*1775838-2AP-S-Pad47)") (class "Default")
      (node (ref "X2*1775838-2") (pin "47") (pinfunction "S_47") (pintype "passive"))
    )
    (net (code "104") (name "unconnected-(X2*1775838-2AQ-S-Pad48)") (class "Default")
      (node (ref "X2*1775838-2") (pin "48") (pinfunction "S_48") (pintype "passive"))
    )
    (net (code "105") (name "unconnected-(X2*1775838-2AR-S-Pad49)") (class "Default")
      (node (ref "X2*1775838-2") (pin "49") (pinfunction "S_49") (pintype "passive"))
    )
    (net (code "106") (name "unconnected-(X2*1775838-2AS-S-Pad5)") (class "Default")
      (node (ref "X2*1775838-2") (pin "5") (pinfunction "S_5") (pintype "passive"))
    )
    (net (code "107") (name "unconnected-(X2*1775838-2AU-S-Pad51)") (class "Default")
      (node (ref "X2*1775838-2") (pin "51") (pinfunction "S_51") (pintype "passive"))
    )
    (net (code "108") (name "unconnected-(X2*1775838-2AW-S-Pad6)") (class "Default")
      (node (ref "X2*1775838-2") (pin "6") (pinfunction "S_6") (pintype "passive"))
    )
    (net (code "109") (name "unconnected-(X2*1775838-2AX-S-Pad7)") (class "Default")
      (node (ref "X2*1775838-2") (pin "7") (pinfunction "S_7") (pintype "passive"))
    )
    (net (code "110") (name "unconnected-(X2*1775838-2C-S-Pad11)") (class "Default")
      (node (ref "X2*1775838-2") (pin "11") (pinfunction "S_11") (pintype "passive"))
    )
    (net (code "111") (name "unconnected-(X2*1775838-2E-S-Pad13)") (class "Default")
      (node (ref "X2*1775838-2") (pin "13") (pinfunction "S_13") (pintype "passive"))
    )
    (net (code "112") (name "unconnected-(X2*1775838-2I-S-Pad17)") (class "Default")
      (node (ref "X2*1775838-2") (pin "17") (pinfunction "S_17") (pintype "passive"))
    )
    (net (code "113") (name "unconnected-(X2*1775838-2K-S-Pad19)") (class "Default")
      (node (ref "X2*1775838-2") (pin "19") (pinfunction "S_19") (pintype "passive"))
    )
    (net (code "114") (name "unconnected-(X2*1775838-2M-S-Pad20)") (class "Default")
      (node (ref "X2*1775838-2") (pin "20") (pinfunction "S_20") (pintype "passive"))
    )
    (net (code "115") (name "unconnected-(X2*1775838-2N-S-Pad21)") (class "Default")
      (node (ref "X2*1775838-2") (pin "21") (pinfunction "S_21") (pintype "passive"))
    )
    (net (code "116") (name "unconnected-(X2*1775838-2O-S-Pad22)") (class "Default")
      (node (ref "X2*1775838-2") (pin "22") (pinfunction "S_22") (pintype "passive"))
    )
    (net (code "117") (name "unconnected-(X2*1775838-2P-S-Pad23)") (class "Default")
      (node (ref "X2*1775838-2") (pin "23") (pinfunction "S_23") (pintype "passive"))
    )
    (net (code "118") (name "unconnected-(X2*1775838-2Q-S-Pad24)") (class "Default")
      (node (ref "X2*1775838-2") (pin "24") (pinfunction "S_24") (pintype "passive"))
    )
    (net (code "119") (name "unconnected-(X2*1775838-2R-S-Pad25)") (class "Default")
      (node (ref "X2*1775838-2") (pin "25") (pinfunction "S_25") (pintype "passive"))
    )
    (net (code "120") (name "unconnected-(X2*1775838-2T-S-Pad27)") (class "Default")
      (node (ref "X2*1775838-2") (pin "27") (pinfunction "S_27") (pintype "passive"))
    )
    (net (code "121") (name "unconnected-(X2*1775838-2U-S-Pad28)") (class "Default")
      (node (ref "X2*1775838-2") (pin "28") (pinfunction "S_28") (pintype "passive"))
    )
    (net (code "122") (name "unconnected-(X2*1775838-2V-S-Pad29)") (class "Default")
      (node (ref "X2*1775838-2") (pin "29") (pinfunction "S_29") (pintype "passive"))
    )
    (net (code "123") (name "unconnected-(X2*1775838-2W-S-Pad3)") (class "Default")
      (node (ref "X2*1775838-2") (pin "3") (pinfunction "S_3") (pintype "passive"))
    )
    (net (code "124") (name "unconnected-(X2*1775838-2X-S-Pad30)") (class "Default")
      (node (ref "X2*1775838-2") (pin "30") (pinfunction "S_30") (pintype "passive"))
    )
    (net (code "125") (name "unconnected-(X2*1775838-2Y-S-Pad31)") (class "Default")
      (node (ref "X2*1775838-2") (pin "31") (pinfunction "S_31") (pintype "passive"))
    )
    (net (code "126") (name "unconnected-(X2*1775838-2Z-S-Pad32)") (class "Default")
      (node (ref "X2*1775838-2") (pin "32") (pinfunction "S_32") (pintype "passive"))
    )
  )
)
